# DATN.net
KiCad netlist of a schematic drawn in Altium Designer
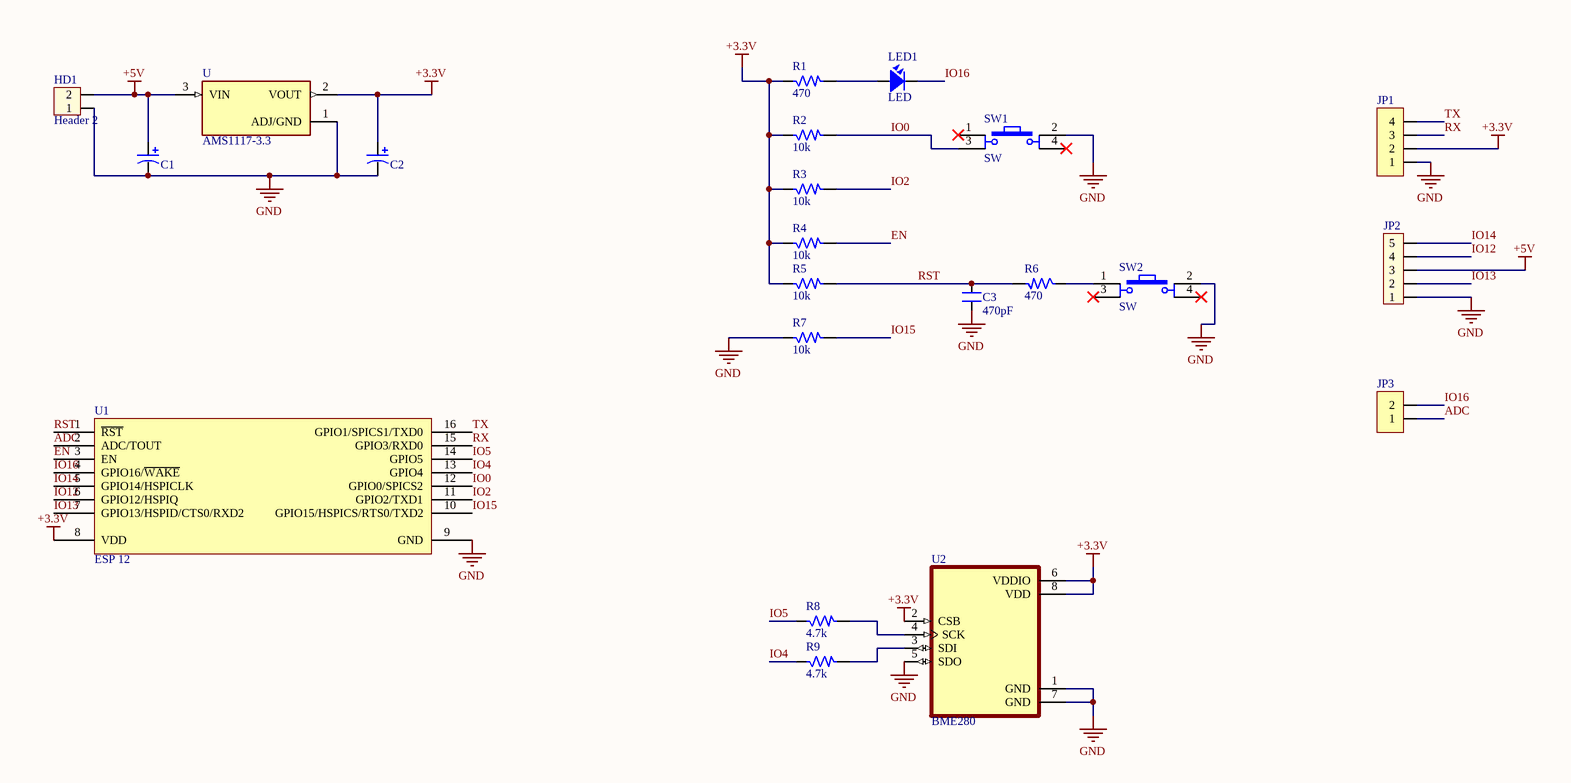
[diagram p0: DATN.SchDoc]

(export (version "E")
  (design (tool "Eeschema 10.0.6"))
  (components
    (comp (ref "C1")
      (value "CAP_TAN_SMD")
      (footprint "CAP_7343")
      (description "Polazied Tantalum Capacitor")
      (libsource (lib "My Library") (part "CAP_TAN_SMD"))
    )
    (comp (ref "C2")
      (value "CAP_TAN_SMD")
      (footprint "CAP_7343")
      (description "Polazied Tantalum Capacitor")
      (libsource (lib "My Library") (part "CAP_TAN_SMD"))
    )
    (comp (ref "C3")
      (value "470pF")
      (footprint "CAP_0805")
      (description "Cap np  1pF - 472pF")
      (libsource (lib "My Library-Mandevice") (part "CN1"))
    )
    (comp (ref "HD1")
      (value "Header 2")
      (footprint "HED2")
      (description "Header 2 (Green)")
      (libsource (lib "My Library-Mandevice") (part "Hed2"))
    )
    (comp (ref "JP1")
      (value "JP4")
      (footprint "JP4-D1C")
      (description "WR-PHD 2.54 mm Angled Socket Header")
      (fields
        (field (name "MANUFACTURER") "Würth Elektronik eiSos GmbH")
        (field (name "PARTNO") "613004143121")
        (field (name "CREATED BY") "Karrer Zheng")
      )
      (libsource (lib "My Library-Mandevice") (part "JP4"))
    )
    (comp (ref "JP2")
      (value "JP5_2")
      (footprint "JP5H")
      (libsource (lib "My Library-Mandevice") (part "JP5_2"))
    )
    (comp (ref "JP3")
      (value "JP2")
      (footprint "JP2-D1T")
      (description "WR-PHD 2.54 mm Angled Socket Header")
      (fields
        (field (name "MANUFACTURER") "Würth Elektronik eiSos GmbH")
        (field (name "PARTNO") "613002143121")
        (field (name "CREATED BY") "Karrer Zheng")
      )
      (libsource (lib "My Library-Mandevice") (part "JP2"))
    )
    (comp (ref "LED1")
      (value "LED")
      (footprint "LED-3")
      (description "LED Single colour Green and Red")
      (libsource (lib "My Library-Mandevice") (part "LED"))
    )
    (comp (ref "R1")
      (value "470")
      (footprint "RES-SMD-0805")
      (description "Resistor 1/4W")
      (libsource (lib "My Library-Mandevice") (part "R"))
    )
    (comp (ref "R2")
      (value "10k")
      (footprint "RES-SMD-0805")
      (description "Resistor 1/4W")
      (libsource (lib "My Library-Mandevice") (part "R"))
    )
    (comp (ref "R3")
      (value "10k")
      (footprint "RES-SMD-0805")
      (description "Resistor 1/4W")
      (libsource (lib "My Library-Mandevice") (part "R"))
    )
    (comp (ref "R4")
      (value "10k")
      (footprint "RES-SMD-0805")
      (description "Resistor 1/4W")
      (libsource (lib "My Library-Mandevice") (part "R"))
    )
    (comp (ref "R5")
      (value "10k")
      (footprint "RES-SMD-0805")
      (description "Resistor 1/4W")
      (libsource (lib "My Library-Mandevice") (part "R"))
    )
    (comp (ref "R6")
      (value "470")
      (footprint "RES-SMD-0805")
      (description "Resistor 1/4W")
      (libsource (lib "My Library-Mandevice") (part "R"))
    )
    (comp (ref "R7")
      (value "10k")
      (footprint "RES-SMD-0805")
      (description "Resistor 1/4W")
      (libsource (lib "My Library-Mandevice") (part "R"))
    )
    (comp (ref "R8")
      (value "4.7k")
      (footprint "RES-SMD-0805")
      (description "Resistor 1/4W")
      (libsource (lib "My Library-Mandevice") (part "R"))
    )
    (comp (ref "R9")
      (value "4.7k")
      (footprint "RES-SMD-0805")
      (description "Resistor 1/4W")
      (libsource (lib "My Library-Mandevice") (part "R"))
    )
    (comp (ref "SW1")
      (value "SW")
      (footprint "SW4")
      (description "Switch button 4 pin")
      (libsource (lib "My Library-Mandevice") (part "SW4"))
    )
    (comp (ref "SW2")
      (value "SW")
      (footprint "SW4")
      (description "Switch button 4 pin")
      (libsource (lib "My Library-Mandevice") (part "SW4"))
    )
    (comp (ref "U")
      (value "AMS1117-3.3")
      (footprint "SOT229P700X180-4N")
      (description "Sot223/Pkg 1-Amp 3.3-Volt Low Drop Out Voltage Regulatator")
      (fields (field (name "MF") "Advanced Monolithic Systems"))
      (libsource (lib "AMS1117") (part "AMS1117-3.3"))
    )
    (comp (ref "U1")
      (value "ESP 12")
      (footprint "ESP12_small")
      (description "ESP-12 Wi-Fi Module by AI-Thinker")
      (libsource (lib "My Library-Mandevice") (part "ESP_12"))
    )
    (comp (ref "U2")
      (value "BME280")
      (footprint "PSON65P250X250X100-8N")
      (libsource (lib "BME280") (part "BME280"))
    )
  )
  (nets
    (net (code "1") (name "+3.3V") (class "Default")
      (node (ref "C2") (pin "1") (pinfunction "1_1") (pintype "passive"))
      (node (ref "JP1") (pin "2") (pinfunction "2_2") (pintype "passive"))
      (node (ref "R1") (pin "1") (pinfunction "1_1") (pintype "passive"))
      (node (ref "R2") (pin "1") (pinfunction "1_1") (pintype "passive"))
      (node (ref "R3") (pin "1") (pinfunction "1_1") (pintype "passive"))
      (node (ref "R4") (pin "1") (pinfunction "1_1") (pintype "passive"))
      (node (ref "R5") (pin "1") (pinfunction "1_1") (pintype "passive"))
      (node (ref "U") (pin "2") (pinfunction "VOUT_2") (pintype "output"))
      (node (ref "U1") (pin "8") (pinfunction "VDD_8") (pintype "passive"))
      (node (ref "U2") (pin "2") (pinfunction "CSB_2") (pintype "input"))
      (node (ref "U2") (pin "6") (pinfunction "VDDIO_6") (pintype "power_in"))
      (node (ref "U2") (pin "8") (pinfunction "VDD_8") (pintype "power_in"))
    )
    (net (code "2") (name "+5V") (class "Default")
      (node (ref "C1") (pin "1") (pinfunction "1_1") (pintype "passive"))
      (node (ref "HD1") (pin "2") (pinfunction "2_2") (pintype "passive"))
      (node (ref "JP2") (pin "3") (pinfunction "3_3") (pintype "passive"))
      (node (ref "U") (pin "3") (pinfunction "VIN_3") (pintype "input"))
    )
    (net (code "3") (name "/ADC") (class "Default")
      (node (ref "JP3") (pin "1") (pinfunction "1_1") (pintype "passive"))
      (node (ref "U1") (pin "2") (pinfunction "ADC/TOUT_2") (pintype "passive"))
    )
    (net (code "4") (name "/EN") (class "Default")
      (node (ref "R4") (pin "2") (pinfunction "2_2") (pintype "passive"))
      (node (ref "U1") (pin "3") (pinfunction "EN_3") (pintype "passive"))
    )
    (net (code "5") (name "/IO0") (class "Default")
      (node (ref "R2") (pin "2") (pinfunction "2_2") (pintype "passive"))
      (node (ref "SW1") (pin "3") (pintype "passive"))
      (node (ref "U1") (pin "12") (pinfunction "GPIO0/SPICS2_12") (pintype "passive"))
    )
    (net (code "6") (name "/IO2") (class "Default")
      (node (ref "R3") (pin "2") (pinfunction "2_2") (pintype "passive"))
      (node (ref "U1") (pin "11") (pinfunction "GPIO2/TXD1_11") (pintype "passive"))
    )
    (net (code "7") (name "/IO4") (class "Default")
      (node (ref "R9") (pin "1") (pinfunction "1_1") (pintype "passive"))
      (node (ref "U1") (pin "13") (pinfunction "GPIO4_13") (pintype "passive"))
    )
    (net (code "8") (name "/IO5") (class "Default")
      (node (ref "R8") (pin "1") (pinfunction "1_1") (pintype "passive"))
      (node (ref "U1") (pin "14") (pinfunction "GPIO5_14") (pintype "passive"))
    )
    (net (code "9") (name "/IO12") (class "Default")
      (node (ref "JP2") (pin "4") (pinfunction "4_4") (pintype "passive"))
      (node (ref "U1") (pin "6") (pinfunction "GPIO12/HSPIQ_6") (pintype "passive"))
    )
    (net (code "10") (name "/IO13") (class "Default")
      (node (ref "JP2") (pin "2") (pinfunction "2_2") (pintype "passive"))
      (node (ref "U1") (pin "7") (pinfunction "GPIO13/HSPID/CTS0/RXD2_7") (pintype "passive"))
    )
    (net (code "11") (name "/IO14") (class "Default")
      (node (ref "JP2") (pin "5") (pinfunction "5_5") (pintype "passive"))
      (node (ref "U1") (pin "5") (pinfunction "GPIO14/HSPICLK_5") (pintype "passive"))
    )
    (net (code "12") (name "/IO15") (class "Default")
      (node (ref "R7") (pin "2") (pinfunction "2_2") (pintype "passive"))
      (node (ref "U1") (pin "10") (pinfunction "GPIO15/HSPICS/RTS0/TXD2_10") (pintype "passive"))
    )
    (net (code "13") (name "/IO16") (class "Default")
      (node (ref "JP3") (pin "2") (pinfunction "2_2") (pintype "passive"))
      (node (ref "LED1") (pin "2") (pinfunction "2_2") (pintype "passive"))
      (node (ref "U1") (pin "4") (pinfunction "GPIO16/~{WAKE}_4") (pintype "passive"))
    )
    (net (code "14") (name "/RST") (class "Default")
      (node (ref "C3") (pin "2") (pinfunction "2_2") (pintype "passive"))
      (node (ref "R5") (pin "2") (pinfunction "2_2") (pintype "passive"))
      (node (ref "R6") (pin "2") (pinfunction "2_2") (pintype "passive"))
      (node (ref "U1") (pin "1") (pinfunction "~{RST}_1") (pintype "passive"))
    )
    (net (code "15") (name "/RX") (class "Default")
      (node (ref "JP1") (pin "3") (pinfunction "3_3") (pintype "passive"))
      (node (ref "U1") (pin "15") (pinfunction "GPIO3/RXD0_15") (pintype "passive"))
    )
    (net (code "16") (name "/TX") (class "Default")
      (node (ref "JP1") (pin "4") (pinfunction "4_4") (pintype "passive"))
      (node (ref "U1") (pin "16") (pinfunction "GPIO1/SPICS1/TXD0_16") (pintype "passive"))
    )
    (net (code "17") (name "GND") (class "Default")
      (node (ref "C1") (pin "2") (pinfunction "2_2") (pintype "passive"))
      (node (ref "C2") (pin "2") (pinfunction "2_2") (pintype "passive"))
      (node (ref "C3") (pin "1") (pinfunction "1_1") (pintype "passive"))
      (node (ref "HD1") (pin "1") (pinfunction "1_1") (pintype "passive"))
      (node (ref "JP1") (pin "1") (pinfunction "1_1") (pintype "passive"))
      (node (ref "JP2") (pin "1") (pinfunction "1_1") (pintype "passive"))
      (node (ref "R7") (pin "1") (pinfunction "1_1") (pintype "passive"))
      (node (ref "SW1") (pin "2") (pintype "passive"))
      (node (ref "SW2") (pin "2") (pintype "passive"))
      (node (ref "U") (pin "1") (pinfunction "ADJ/GND_1") (pintype "power_in"))
      (node (ref "U1") (pin "9") (pinfunction "GND_9") (pintype "passive"))
      (node (ref "U2") (pin "1") (pinfunction "GND_1") (pintype "power_in"))
      (node (ref "U2") (pin "5") (pinfunction "SDO_5") (pintype "bidirectional"))
      (node (ref "U2") (pin "7") (pinfunction "GND_7") (pintype "power_in"))
    )
    (net (code "18") (name "Net-(LED1-Pad1)") (class "Default")
      (node (ref "LED1") (pin "1") (pinfunction "1_1") (pintype "passive"))
      (node (ref "R1") (pin "2") (pinfunction "2_2") (pintype "passive"))
    )
    (net (code "19") (name "Net-(R6-Pad1)") (class "Default")
      (node (ref "R6") (pin "1") (pinfunction "1_1") (pintype "passive"))
      (node (ref "SW2") (pin "1") (pintype "passive"))
    )
    (net (code "20") (name "Net-(U2-SCK)") (class "Default")
      (node (ref "R8") (pin "2") (pinfunction "2_2") (pintype "passive"))
      (node (ref "U2") (pin "4") (pinfunction "SCK_4") (pintype "input"))
    )
    (net (code "21") (name "Net-(U2-SDI)") (class "Default")
      (node (ref "R9") (pin "2") (pinfunction "2_2") (pintype "passive"))
      (node (ref "U2") (pin "3") (pinfunction "SDI_3") (pintype "bidirectional"))
    )
    (net (code "22") (name "unconnected-(SW1-Pad1)") (class "Default")
      (node (ref "SW1") (pin "1") (pintype "passive+no_connect"))
    )
    (net (code "23") (name "unconnected-(SW1-Pad4)") (class "Default")
      (node (ref "SW1") (pin "4") (pintype "passive+no_connect"))
    )
    (net (code "24") (name "unconnected-(SW2-Pad3)") (class "Default")
      (node (ref "SW2") (pin "3") (pintype "passive+no_connect"))
    )
    (net (code "25") (name "unconnected-(SW2-Pad4)") (class "Default")
      (node (ref "SW2") (pin "4") (pintype "passive+no_connect"))
    )
  )
)
